# User_LEDs.net
KiCad netlist of a schematic drawn in Altium Designer
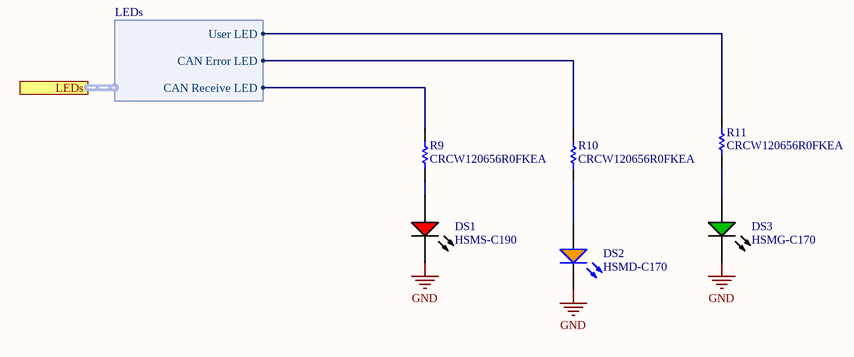
[diagram p0: User_LEDs.SchDoc]

(export (version "E")
  (design (tool "Eeschema 10.0.6"))
  (components
    (comp (ref "DS1")
      (value "HSMS-C190")
      (footprint "AVAG-HSMX-C190_V")
      (description "LED Uni-Color Red, 52 mW, 20 mA, -40 to 85 degC, 2-Pin SMD, RoHS, Tape and Reel")
      (fields (field (name "MANUFACTURER") "Avago"))
      (libsource (lib "Altium Content Vault") (part "LED-RED-AK-2"))
    )
    (comp (ref "DS2")
      (value "HSMD-C170")
      (footprint "AVAG-HSMX-C170_V")
      (description "LED Uni-Color Orange, 52 mW, 20 mA, -40 to 85 degC, 2-Pin SMD, RoHS, Tape and Reel")
      (fields (field (name "MANUFACTURER") "Avago"))
      (libsource (lib "Altium Content Vault") (part "LED-ORANGE-AK-2"))
    )
    (comp (ref "DS3")
      (value "HSMG-C170")
      (footprint "AVAG-HSMX-C170_V")
      (description "Chip LED, Green, 2.2 V, -40 to 85 degC, 2-Pin SMD, Pb-Free, Tape and Reel")
      (fields (field (name "MANUFACTURER") "Avago"))
      (libsource (lib "Altium Content Vault") (part "LED_GREEN_A1K2-2"))
    )
    (comp (ref "R9")
      (value "CRCW120656R0FKEA")
      (footprint "RESC3216X60X45LL10T20")
      (fields (field (name "MANUFACTURER") "Vishay Dale"))
      (libsource (lib "Altium Content Vault") (part "RES"))
    )
    (comp (ref "R10")
      (value "CRCW120656R0FKEA")
      (footprint "RESC3216X60X45LL10T20")
      (fields (field (name "MANUFACTURER") "Vishay Dale"))
      (libsource (lib "Altium Content Vault") (part "RES"))
    )
    (comp (ref "R11")
      (value "CRCW120656R0FKEA")
      (footprint "RESC3216X60X45LL10T20")
      (fields (field (name "MANUFACTURER") "Vishay Dale"))
      (libsource (lib "Altium Content Vault") (part "RES"))
    )
  )
  (nets
    (net (code "2") (name "/CAN Error LED") (class "Default")
      (node (ref "R10") (pin "2") (pinfunction "2_2") (pintype "passive"))
    )
    (net (code "3") (name "/CAN Receive LED") (class "Default")
      (node (ref "R9") (pin "2") (pinfunction "2_2") (pintype "passive"))
    )
    (net (code "4") (name "/User LED") (class "Default")
      (node (ref "R11") (pin "2") (pinfunction "2_2") (pintype "passive"))
    )
    (net (code "6") (name "GND") (class "Default")
      (node (ref "DS1") (pin "2") (pinfunction "K_2") (pintype "passive"))
      (node (ref "DS2") (pin "2") (pinfunction "K_2") (pintype "passive"))
      (node (ref "DS3") (pin "2") (pinfunction "K_2") (pintype "passive"))
    )
    (net (code "7") (name "Net-(DS1-A)") (class "Default")
      (node (ref "DS1") (pin "1") (pinfunction "A_1") (pintype "passive"))
      (node (ref "R9") (pin "1") (pinfunction "1_1") (pintype "passive"))
    )
    (net (code "8") (name "Net-(DS2-A)") (class "Default")
      (node (ref "DS2") (pin "1") (pinfunction "A_1") (pintype "passive"))
      (node (ref "R10") (pin "1") (pinfunction "1_1") (pintype "passive"))
    )
    (net (code "9") (name "Net-(DS3-A)") (class "Default")
      (node (ref "DS3") (pin "1") (pinfunction "A_1") (pintype "passive"))
      (node (ref "R11") (pin "1") (pinfunction "1_1") (pintype "passive"))
    )
  )
)
